# SCH_Logette_connect__2023-11-30.net
KiCad netlist of a schematic drawn in EasyEDA
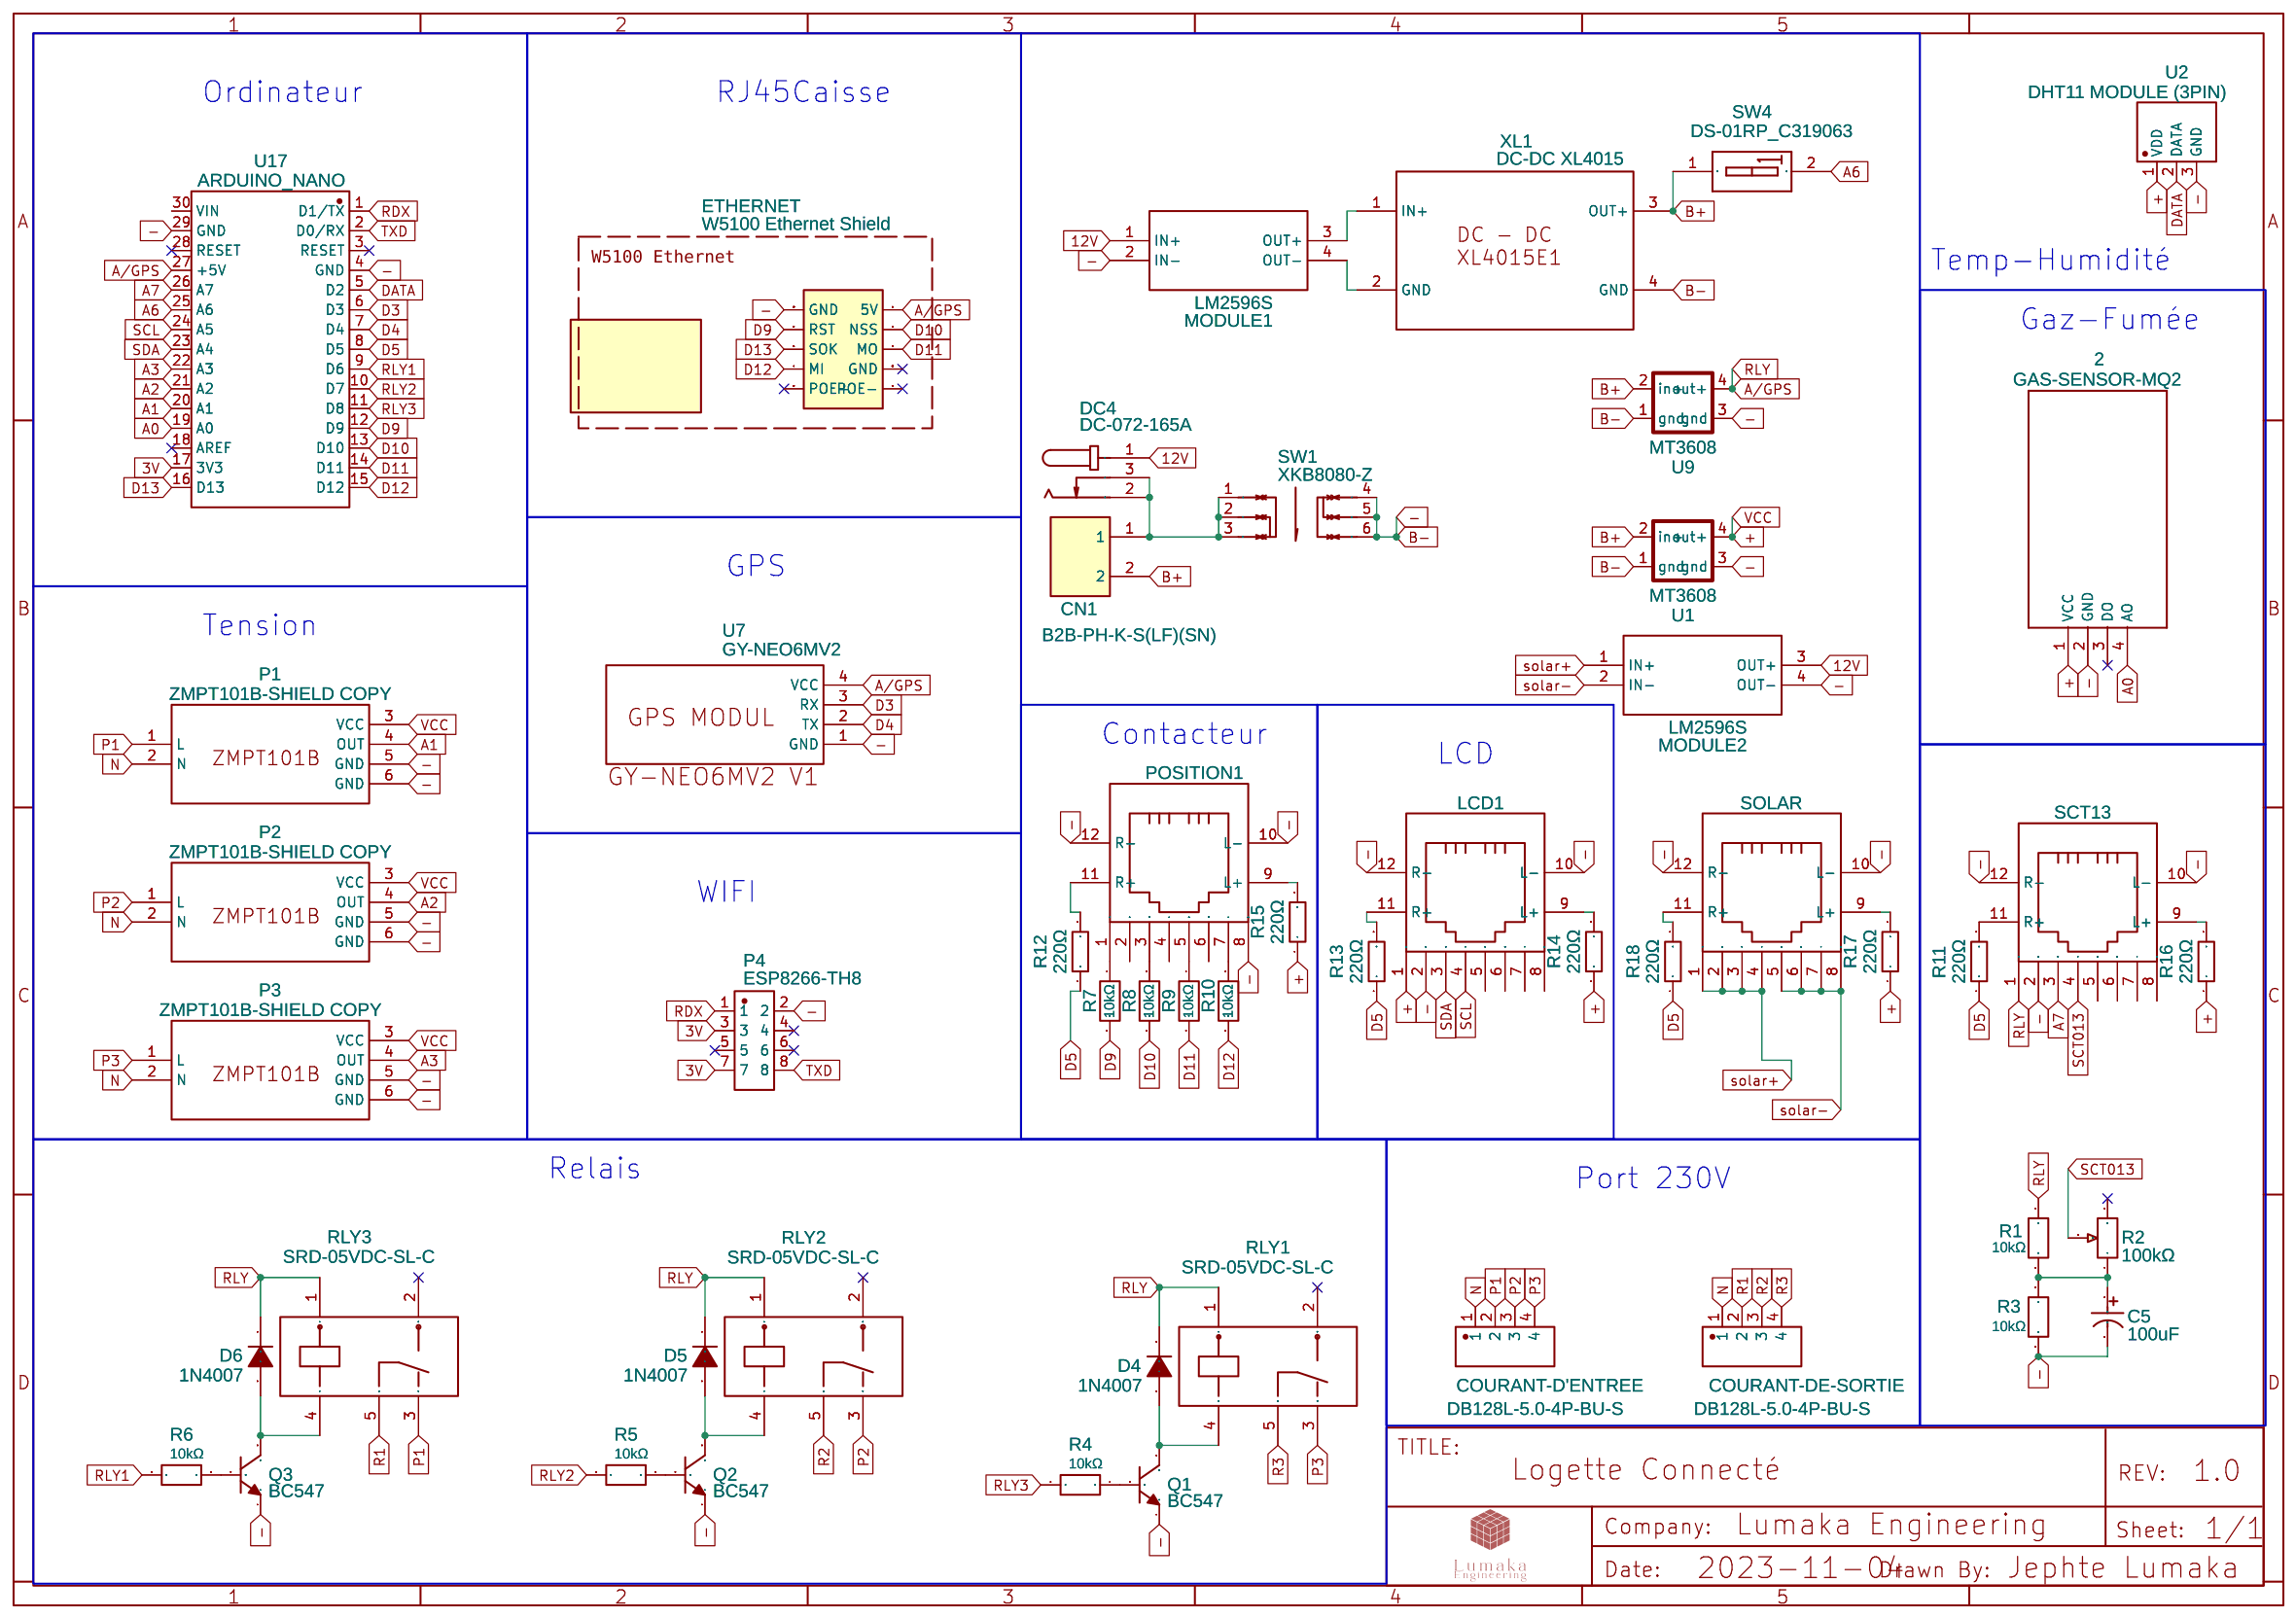
[diagram p0: schematic sheet]

(export (version "E")
  (design (tool "Eeschema 10.0.6"))
  (components
    (comp (ref "2") (value "GAS-SENSOR-MQ2") (libsource (lib "") (part "GAS-SENSOR-MQ2")))
    (comp (ref "C5")
      (value "100uF")
      (fields
        (field (name "Manufacturer Part") "UWX1C101MCL1GB")
        (field (name "Manufacturer") "Nichicon(尼吉康)")
      )
      (libsource (lib "") (part "UWX1C101MCL1GB"))
    )
    (comp (ref "CN1")
      (value "B2B-PH-K-S(LF)(SN)")
      (fields (field (name "Manufacturer") "JST"))
      (libsource (lib "") (part "B2B-PH-K-S(LF)(SN)"))
    )
    (comp (ref "COURANT-D'ENTREE")
      (value "DB128L-5.0-4P-BU-S")
      (fields (field (name "Manufacturer") "DIBO(地博电气)"))
      (libsource (lib "") (part "DB128L-5.0-4P-BU-S_1"))
    )
    (comp (ref "COURANT-DE-SORTIE")
      (value "DB128L-5.0-4P-BU-S")
      (fields (field (name "Manufacturer") "DIBO(地博电气)"))
      (libsource (lib "") (part "DB128L-5.0-4P-BU-S"))
    )
    (comp (ref "D4")
      (value "1N4007")
      (fields (field (name "Manufacturer Part") "1N4007E-E3/54") (field (name "Manufacturer") "VISHAY(威世)"))
      (libsource (lib "") (part "1N4007E-E3/54"))
    )
    (comp (ref "D5")
      (value "1N4007")
      (fields (field (name "Manufacturer Part") "1N4007E-E3/54") (field (name "Manufacturer") "VISHAY(威世)"))
      (libsource (lib "") (part "1N4007E-E3/54"))
    )
    (comp (ref "D6")
      (value "1N4007")
      (fields (field (name "Manufacturer Part") "1N4007E-E3/54") (field (name "Manufacturer") "VISHAY(威世)"))
      (libsource (lib "") (part "1N4007E-E3/54"))
    )
    (comp (ref "DC4")
      (value "DC-072-165A")
      (fields (field (name "Manufacturer") "HRO"))
      (libsource (lib "") (part "DC-072-165A"))
    )
    (comp (ref "ETHERNET")
      (value "W5100 Ethernet Shield")
      (libsource (lib "") (part "W5100 Ethernet Shield"))
    )
    (comp (ref "LCD1")
      (value "MJ5688-Y011-GRNL1")
      (fields (field (name "Manufacturer") "Heling(合陵)"))
      (libsource (lib "") (part "MJ5688-Y011-GRNL1_3"))
    )
    (comp (ref "MODULE1")
      (value "LM2596S")
      (fields (field (name "Manufacturer Part") "LM2596"))
      (libsource (lib "") (part "LM2596S"))
    )
    (comp (ref "MODULE2")
      (value "LM2596S")
      (fields (field (name "Manufacturer Part") "LM2596"))
      (libsource (lib "") (part "LM2596S"))
    )
    (comp (ref "P1")
      (value "ZMPT101B-SHIELD COPY")
      (fields (field (name "Manufacturer") "sterling"))
      (libsource (lib "") (part "ZMPT101B-SHIELD COPY"))
    )
    (comp (ref "P2")
      (value "ZMPT101B-SHIELD COPY")
      (fields (field (name "Manufacturer") "sterling"))
      (libsource (lib "") (part "ZMPT101B-SHIELD COPY"))
    )
    (comp (ref "P3")
      (value "ZMPT101B-SHIELD COPY")
      (fields (field (name "Manufacturer") "sterling"))
      (libsource (lib "") (part "ZMPT101B-SHIELD COPY"))
    )
    (comp (ref "P4") (value "ESP8266-TH8") (libsource (lib "") (part "ESP8266-TH8")))
    (comp (ref "POSITION1")
      (value "MJ5688-Y011-GRNL1")
      (fields (field (name "Manufacturer") "Heling(合陵)"))
      (libsource (lib "") (part "MJ5688-Y011-GRNL1_1"))
    )
    (comp (ref "Q1") (value "BC547") (libsource (lib "") (part "BC547COPY")))
    (comp (ref "Q2") (value "BC547") (libsource (lib "") (part "BC547COPY")))
    (comp (ref "Q3") (value "BC547") (libsource (lib "") (part "BC547COPY")))
    (comp (ref "R1")
      (value "10kΩ")
      (fields
        (field (name "Manufacturer Part") "MF1/4W-100KΩ±1%T52")
        (field (name "Manufacturer") "Huaxing Mechanical-Elec.")
      )
      (libsource (lib "") (part "MF1/4W-100KΩ±1%T52"))
    )
    (comp (ref "R2")
      (value "100kΩ")
      (fields (field (name "Manufacturer Part") "3296W-1-104") (field (name "Manufacturer") "BOCHEN(博晨)"))
      (libsource (lib "") (part "3296W-1-104"))
    )
    (comp (ref "R3")
      (value "10kΩ")
      (fields
        (field (name "Manufacturer Part") "MF1/4W-100KΩ±1%T52")
        (field (name "Manufacturer") "Huaxing Mechanical-Elec.")
      )
      (libsource (lib "") (part "MF1/4W-100KΩ±1%T52"))
    )
    (comp (ref "R4")
      (value "10kΩ")
      (fields
        (field (name "Manufacturer Part") "MF1/4W-100KΩ±1%T52")
        (field (name "Manufacturer") "Huaxing Mechanical-Elec.")
      )
      (libsource (lib "") (part "MF1/4W-100KΩ±1%T52_1"))
    )
    (comp (ref "R5")
      (value "10kΩ")
      (fields
        (field (name "Manufacturer Part") "MF1/4W-100KΩ±1%T52")
        (field (name "Manufacturer") "Huaxing Mechanical-Elec.")
      )
      (libsource (lib "") (part "MF1/4W-100KΩ±1%T52_1"))
    )
    (comp (ref "R6")
      (value "10kΩ")
      (fields
        (field (name "Manufacturer Part") "MF1/4W-100KΩ±1%T52")
        (field (name "Manufacturer") "Huaxing Mechanical-Elec.")
      )
      (libsource (lib "") (part "MF1/4W-100KΩ±1%T52_1"))
    )
    (comp (ref "R7")
      (value "10kΩ")
      (fields
        (field (name "Manufacturer Part") "MF1/4W-100KΩ±1%T52")
        (field (name "Manufacturer") "Huaxing Mechanical-Elec.")
      )
      (libsource (lib "") (part "MF1/4W-100KΩ±1%T52"))
    )
    (comp (ref "R8")
      (value "10kΩ")
      (fields
        (field (name "Manufacturer Part") "MF1/4W-100KΩ±1%T52")
        (field (name "Manufacturer") "Huaxing Mechanical-Elec.")
      )
      (libsource (lib "") (part "MF1/4W-100KΩ±1%T52"))
    )
    (comp (ref "R9")
      (value "10kΩ")
      (fields
        (field (name "Manufacturer Part") "MF1/4W-100KΩ±1%T52")
        (field (name "Manufacturer") "Huaxing Mechanical-Elec.")
      )
      (libsource (lib "") (part "MF1/4W-100KΩ±1%T52"))
    )
    (comp (ref "R10")
      (value "10kΩ")
      (fields
        (field (name "Manufacturer Part") "MF1/4W-100KΩ±1%T52")
        (field (name "Manufacturer") "Huaxing Mechanical-Elec.")
      )
      (libsource (lib "") (part "MF1/4W-100KΩ±1%T52"))
    )
    (comp (ref "R11")
      (value "220Ω")
      (fields
        (field (name "Manufacturer Part") "MFR0W4F2200A50")
        (field (name "Manufacturer") "UNI-ROYAL(厚声)")
      )
      (libsource (lib "") (part "MFR0W4F2200A50"))
    )
    (comp (ref "R12")
      (value "220Ω")
      (fields
        (field (name "Manufacturer Part") "MFR0W4F2200A50")
        (field (name "Manufacturer") "UNI-ROYAL(厚声)")
      )
      (libsource (lib "") (part "MFR0W4F2200A50"))
    )
    (comp (ref "R13")
      (value "220Ω")
      (fields
        (field (name "Manufacturer Part") "MFR0W4F2200A50")
        (field (name "Manufacturer") "UNI-ROYAL(厚声)")
      )
      (libsource (lib "") (part "MFR0W4F2200A50"))
    )
    (comp (ref "R14")
      (value "220Ω")
      (fields
        (field (name "Manufacturer Part") "MFR0W4F2200A50")
        (field (name "Manufacturer") "UNI-ROYAL(厚声)")
      )
      (libsource (lib "") (part "MFR0W4F2200A50"))
    )
    (comp (ref "R15")
      (value "220Ω")
      (fields
        (field (name "Manufacturer Part") "MFR0W4F2200A50")
        (field (name "Manufacturer") "UNI-ROYAL(厚声)")
      )
      (libsource (lib "") (part "MFR0W4F2200A50"))
    )
    (comp (ref "R16")
      (value "220Ω")
      (fields
        (field (name "Manufacturer Part") "MFR0W4F2200A50")
        (field (name "Manufacturer") "UNI-ROYAL(厚声)")
      )
      (libsource (lib "") (part "MFR0W4F2200A50"))
    )
    (comp (ref "R17")
      (value "220Ω")
      (fields
        (field (name "Manufacturer Part") "MFR0W4F2200A50")
        (field (name "Manufacturer") "UNI-ROYAL(厚声)")
      )
      (libsource (lib "") (part "MFR0W4F2200A50"))
    )
    (comp (ref "R18")
      (value "220Ω")
      (fields
        (field (name "Manufacturer Part") "MFR0W4F2200A50")
        (field (name "Manufacturer") "UNI-ROYAL(厚声)")
      )
      (libsource (lib "") (part "MFR0W4F2200A50"))
    )
    (comp (ref "RLY1")
      (value "SRD-05VDC-SL-C")
      (fields (field (name "Manufacturer") "松乐"))
      (libsource (lib "") (part "SRD-05VDC-SL-C"))
    )
    (comp (ref "RLY2")
      (value "SRD-05VDC-SL-C")
      (fields (field (name "Manufacturer") "松乐"))
      (libsource (lib "") (part "SRD-05VDC-SL-C"))
    )
    (comp (ref "RLY3")
      (value "SRD-05VDC-SL-C")
      (fields (field (name "Manufacturer") "松乐"))
      (libsource (lib "") (part "SRD-05VDC-SL-C"))
    )
    (comp (ref "SCT13")
      (value "MJ5688-Y011-GRNL1")
      (fields (field (name "Manufacturer") "Heling(合陵)"))
      (libsource (lib "") (part "MJ5688-Y011-GRNL1"))
    )
    (comp (ref "SOLAR")
      (value "MJ5688-Y011-GRNL1")
      (fields (field (name "Manufacturer") "Heling(合陵)"))
      (libsource (lib "") (part "MJ5688-Y011-GRNL1_2"))
    )
    (comp (ref "SW1")
      (value "XKB8080-Z")
      (fields (field (name "Manufacturer") "XKB Enterprise"))
      (libsource (lib "") (part "XKB8080-Z"))
    )
    (comp (ref "SW4")
      (value "DS-01RP_C319063")
      (fields (field (name "Manufacturer Part") "DS-01RP") (field (name "Manufacturer") "XKB Enterprise"))
      (libsource (lib "") (part "DS-01RP_C319063"))
    )
    (comp (ref "U1")
      (value "MT3608")
      (fields (field (name "Manufacturer Part") "dc/dc"))
      (libsource (lib "") (part "dc dc"))
    )
    (comp (ref "U2")
      (value "DHT11 MODULE (3PIN)")
      (fields
        (field (name "Manufacturer Part") "DHT11")
        (field (name "Manufacturer") "Aosong (Guangzhou) Elec")
      )
      (libsource (lib "") (part "DHT11 MODULE (3PIN)"))
    )
    (comp (ref "U7") (value "GY-NEO6MV2") (libsource (lib "") (part "GY-NEO6MV2")))
    (comp (ref "U9")
      (value "MT3608")
      (fields (field (name "Manufacturer Part") "dc/dc"))
      (libsource (lib "") (part "dc dc"))
    )
    (comp (ref "U17") (value "ARDUINO_NANO") (libsource (lib "") (part "ARDUINO_NANO")))
    (comp (ref "XL1") (value "DC-DC XL4015") (libsource (lib "") (part "DC-DC XL4015")))
  )
  (nets
    (net (code "1") (name "+") (class "Default")
      (node (ref "2") (pin "1") (pinfunction "VCC_1") (pintype "bidirectional"))
      (node (ref "LCD1") (pin "1") (pinfunction "1_1") (pintype "unspecified"))
      (node (ref "P1") (pin "3") (pinfunction "VCC_3") (pintype "unspecified"))
      (node (ref "P2") (pin "3") (pinfunction "VCC_3") (pintype "unspecified"))
      (node (ref "P3") (pin "3") (pinfunction "VCC_3") (pintype "unspecified"))
      (node (ref "R14") (pin "1") (pinfunction "1_1") (pintype "input"))
      (node (ref "R15") (pin "1") (pinfunction "1_1") (pintype "input"))
      (node (ref "R16") (pin "1") (pinfunction "1_1") (pintype "input"))
      (node (ref "R17") (pin "1") (pinfunction "1_1") (pintype "input"))
      (node (ref "U1") (pin "4") (pinfunction "out+_4") (pintype "unspecified"))
      (node (ref "U2") (pin "1") (pinfunction "VDD_1") (pintype "unspecified"))
    )
    (net (code "2") (name "-") (class "Default")
      (node (ref "2") (pin "2") (pinfunction "GND_2") (pintype "bidirectional"))
      (node (ref "C5") (pin "2") (pinfunction "2_2") (pintype "input"))
      (node (ref "ETHERNET") (pin "GND_1") (pinfunction "GND_GND_1") (pintype "unspecified"))
      (node (ref "LCD1") (pin "10") (pinfunction "L-_10") (pintype "unspecified"))
      (node (ref "LCD1") (pin "12") (pinfunction "R-_12") (pintype "unspecified"))
      (node (ref "LCD1") (pin "2") (pinfunction "2_2") (pintype "unspecified"))
      (node (ref "MODULE1") (pin "2") (pinfunction "IN-_2") (pintype "input"))
      (node (ref "MODULE2") (pin "4") (pinfunction "OUT-_4") (pintype "output"))
      (node (ref "P1") (pin "5") (pinfunction "GND_5") (pintype "unspecified"))
      (node (ref "P1") (pin "6") (pinfunction "GND_6") (pintype "unspecified"))
      (node (ref "P2") (pin "5") (pinfunction "GND_5") (pintype "unspecified"))
      (node (ref "P2") (pin "6") (pinfunction "GND_6") (pintype "unspecified"))
      (node (ref "P3") (pin "5") (pinfunction "GND_5") (pintype "unspecified"))
      (node (ref "P3") (pin "6") (pinfunction "GND_6") (pintype "unspecified"))
      (node (ref "P4") (pin "2") (pinfunction "2_2") (pintype "unspecified"))
      (node (ref "POSITION1") (pin "10") (pinfunction "L-_10") (pintype "unspecified"))
      (node (ref "POSITION1") (pin "12") (pinfunction "R-_12") (pintype "unspecified"))
      (node (ref "POSITION1") (pin "8") (pinfunction "8_8") (pintype "unspecified"))
      (node (ref "Q1") (pin "1") (pinfunction "E_1") (pintype "unspecified"))
      (node (ref "Q2") (pin "1") (pinfunction "E_1") (pintype "unspecified"))
      (node (ref "Q3") (pin "1") (pinfunction "E_1") (pintype "unspecified"))
      (node (ref "R3") (pin "2") (pinfunction "2_2") (pintype "unspecified"))
      (node (ref "SCT13") (pin "10") (pinfunction "L-_10") (pintype "unspecified"))
      (node (ref "SCT13") (pin "12") (pinfunction "R-_12") (pintype "unspecified"))
      (node (ref "SCT13") (pin "2") (pinfunction "2_2") (pintype "unspecified"))
      (node (ref "SOLAR") (pin "10") (pinfunction "L-_10") (pintype "unspecified"))
      (node (ref "SOLAR") (pin "12") (pinfunction "R-_12") (pintype "unspecified"))
      (node (ref "SW1") (pin "4") (pinfunction "4_4") (pintype "unspecified"))
      (node (ref "SW1") (pin "5") (pinfunction "5_5") (pintype "unspecified"))
      (node (ref "SW1") (pin "6") (pinfunction "6_6") (pintype "unspecified"))
      (node (ref "U1") (pin "1") (pinfunction "gnd_1") (pintype "unspecified"))
      (node (ref "U1") (pin "3") (pinfunction "gnd_3") (pintype "unspecified"))
      (node (ref "U17") (pin "29") (pinfunction "GND_29") (pintype "unspecified"))
      (node (ref "U17") (pin "4") (pinfunction "GND_4") (pintype "unspecified"))
      (node (ref "U2") (pin "3") (pinfunction "GND_3") (pintype "unspecified"))
      (node (ref "U7") (pin "1") (pinfunction "GND_1") (pintype "passive"))
      (node (ref "U9") (pin "1") (pinfunction "gnd_1") (pintype "unspecified"))
      (node (ref "U9") (pin "3") (pinfunction "gnd_3") (pintype "unspecified"))
      (node (ref "XL1") (pin "4") (pinfunction "GND_4") (pintype "unspecified"))
    )
    (net (code "3") (name "3V") (class "Default")
      (node (ref "P4") (pin "3") (pinfunction "3_3") (pintype "unspecified"))
      (node (ref "P4") (pin "7") (pinfunction "7_7") (pintype "unspecified"))
      (node (ref "U17") (pin "17") (pinfunction "3V3_17") (pintype "unspecified"))
    )
    (net (code "4") (name "12V") (class "Default")
      (node (ref "DC4") (pin "1") (pinfunction "1_1") (pintype "unspecified"))
      (node (ref "MODULE1") (pin "1") (pinfunction "IN+_1") (pintype "input"))
      (node (ref "MODULE2") (pin "3") (pinfunction "OUT+_3") (pintype "output"))
    )
    (net (code "5") (name "A0") (class "Default")
      (node (ref "2") (pin "4") (pinfunction "AO_4") (pintype "bidirectional"))
      (node (ref "U17") (pin "19") (pinfunction "A0_19") (pintype "unspecified"))
    )
    (net (code "6") (name "A1") (class "Default")
      (node (ref "P1") (pin "4") (pinfunction "OUT_4") (pintype "unspecified"))
      (node (ref "U17") (pin "20") (pinfunction "A1_20") (pintype "unspecified"))
    )
    (net (code "7") (name "A2") (class "Default")
      (node (ref "P2") (pin "4") (pinfunction "OUT_4") (pintype "unspecified"))
      (node (ref "U17") (pin "21") (pinfunction "A2_21") (pintype "unspecified"))
    )
    (net (code "8") (name "A3") (class "Default")
      (node (ref "P3") (pin "4") (pinfunction "OUT_4") (pintype "unspecified"))
      (node (ref "U17") (pin "22") (pinfunction "A3_22") (pintype "unspecified"))
    )
    (net (code "9") (name "A6") (class "Default")
      (node (ref "SW4") (pin "2") (pinfunction "A2_2") (pintype "input"))
      (node (ref "U17") (pin "25") (pinfunction "A6_25") (pintype "unspecified"))
    )
    (net (code "10") (name "A7") (class "Default")
      (node (ref "SCT13") (pin "3") (pinfunction "3_3") (pintype "unspecified"))
      (node (ref "U17") (pin "26") (pinfunction "A7_26") (pintype "unspecified"))
    )
    (net (code "11") (name "A{slash}GPS") (class "Default")
      (node (ref "D4") (pin "1") (pinfunction "K_1") (pintype "unspecified"))
      (node (ref "D5") (pin "1") (pinfunction "K_1") (pintype "unspecified"))
      (node (ref "D6") (pin "1") (pinfunction "K_1") (pintype "unspecified"))
      (node (ref "ETHERNET") (pin "5V") (pinfunction "5V_5V") (pintype "unspecified"))
      (node (ref "R1") (pin "1") (pinfunction "1_1") (pintype "unspecified"))
      (node (ref "RLY1") (pin "1") (pinfunction "1_1") (pintype "input"))
      (node (ref "RLY2") (pin "1") (pinfunction "1_1") (pintype "input"))
      (node (ref "RLY3") (pin "1") (pinfunction "1_1") (pintype "input"))
      (node (ref "SCT13") (pin "1") (pinfunction "1_1") (pintype "unspecified"))
      (node (ref "U17") (pin "27") (pinfunction "+5V_27") (pintype "unspecified"))
      (node (ref "U7") (pin "4") (pinfunction "VCC_4") (pintype "passive"))
      (node (ref "U9") (pin "4") (pinfunction "out+_4") (pintype "unspecified"))
    )
    (net (code "12") (name "B+") (class "Default")
      (node (ref "CN1") (pin "2") (pinfunction "2_2") (pintype "input"))
      (node (ref "SW4") (pin "1") (pinfunction "A1_1") (pintype "input"))
      (node (ref "U1") (pin "2") (pinfunction "in+_2") (pintype "unspecified"))
      (node (ref "U9") (pin "2") (pinfunction "in+_2") (pintype "unspecified"))
      (node (ref "XL1") (pin "3") (pinfunction "OUT+_3") (pintype "passive"))
    )
    (net (code "13") (name "D3") (class "Default")
      (node (ref "U17") (pin "6") (pinfunction "D3_6") (pintype "unspecified"))
      (node (ref "U7") (pin "3") (pinfunction "RX_3") (pintype "input"))
    )
    (net (code "14") (name "D4") (class "Default")
      (node (ref "U17") (pin "7") (pinfunction "D4_7") (pintype "unspecified"))
      (node (ref "U7") (pin "2") (pinfunction "TX_2") (pintype "output"))
    )
    (net (code "15") (name "D5") (class "Default")
      (node (ref "R11") (pin "1") (pinfunction "1_1") (pintype "input"))
      (node (ref "R12") (pin "1") (pinfunction "1_1") (pintype "input"))
      (node (ref "R13") (pin "1") (pinfunction "1_1") (pintype "input"))
      (node (ref "R18") (pin "1") (pinfunction "1_1") (pintype "input"))
      (node (ref "U17") (pin "8") (pinfunction "D5_8") (pintype "unspecified"))
    )
    (net (code "16") (name "D9") (class "Default")
      (node (ref "ETHERNET") (pin "RST") (pinfunction "RST_RST") (pintype "unspecified"))
      (node (ref "R7") (pin "2") (pinfunction "2_2") (pintype "unspecified"))
      (node (ref "U17") (pin "12") (pinfunction "D9_12") (pintype "unspecified"))
    )
    (net (code "17") (name "D10") (class "Default")
      (node (ref "ETHERNET") (pin "NSS") (pinfunction "NSS_NSS") (pintype "unspecified"))
      (node (ref "R8") (pin "2") (pinfunction "2_2") (pintype "unspecified"))
      (node (ref "U17") (pin "13") (pinfunction "D10_13") (pintype "unspecified"))
    )
    (net (code "18") (name "D11") (class "Default")
      (node (ref "ETHERNET") (pin "MO") (pinfunction "MO_MO") (pintype "unspecified"))
      (node (ref "R9") (pin "2") (pinfunction "2_2") (pintype "unspecified"))
      (node (ref "U17") (pin "14") (pinfunction "D11_14") (pintype "unspecified"))
    )
    (net (code "19") (name "D12") (class "Default")
      (node (ref "ETHERNET") (pin "MI") (pinfunction "MI_MI") (pintype "unspecified"))
      (node (ref "R10") (pin "2") (pinfunction "2_2") (pintype "unspecified"))
      (node (ref "U17") (pin "15") (pinfunction "D12_15") (pintype "unspecified"))
    )
    (net (code "20") (name "D13") (class "Default")
      (node (ref "ETHERNET") (pin "SOK") (pinfunction "SOK_SOK") (pintype "unspecified"))
      (node (ref "U17") (pin "16") (pinfunction "D13_16") (pintype "unspecified"))
    )
    (net (code "21") (name "DATA") (class "Default")
      (node (ref "U17") (pin "5") (pinfunction "D2_5") (pintype "unspecified"))
      (node (ref "U2") (pin "2") (pinfunction "DATA_2") (pintype "unspecified"))
    )
    (net (code "22") (name "N") (class "Default")
      (node (ref "COURANT-D'ENTREE") (pin "1") (pinfunction "1_1") (pintype "unspecified"))
      (node (ref "COURANT-DE-SORTIE") (pin "1") (pinfunction "1_1") (pintype "unspecified"))
      (node (ref "P1") (pin "2") (pinfunction "N_2") (pintype "unspecified"))
      (node (ref "P2") (pin "2") (pinfunction "N_2") (pintype "unspecified"))
      (node (ref "P3") (pin "2") (pinfunction "N_2") (pintype "unspecified"))
    )
    (net (code "23") (name "Net-(C5-Pad1)") (class "Default")
      (node (ref "C5") (pin "1") (pinfunction "1_1") (pintype "input"))
      (node (ref "R1") (pin "2") (pinfunction "2_2") (pintype "unspecified"))
      (node (ref "R2") (pin "1") (pinfunction "1_1") (pintype "input"))
      (node (ref "R3") (pin "1") (pinfunction "1_1") (pintype "unspecified"))
    )
    (net (code "24") (name "Net-(CN1-Pad1)") (class "Default")
      (node (ref "CN1") (pin "1") (pinfunction "1_1") (pintype "input"))
      (node (ref "DC4") (pin "2") (pinfunction "2_2") (pintype "unspecified"))
      (node (ref "DC4") (pin "3") (pinfunction "3_3") (pintype "unspecified"))
      (node (ref "SW1") (pin "1") (pinfunction "1_1") (pintype "unspecified"))
      (node (ref "SW1") (pin "2") (pinfunction "2_2") (pintype "unspecified"))
      (node (ref "SW1") (pin "3") (pinfunction "3_3") (pintype "unspecified"))
    )
    (net (code "25") (name "Net-(D4-A)") (class "Default")
      (node (ref "D4") (pin "2") (pinfunction "A_2") (pintype "unspecified"))
      (node (ref "Q1") (pin "3") (pinfunction "C_3") (pintype "unspecified"))
      (node (ref "RLY1") (pin "4") (pinfunction "4_4") (pintype "input"))
    )
    (net (code "26") (name "Net-(D5-A)") (class "Default")
      (node (ref "D5") (pin "2") (pinfunction "A_2") (pintype "unspecified"))
      (node (ref "Q2") (pin "3") (pinfunction "C_3") (pintype "unspecified"))
      (node (ref "RLY2") (pin "4") (pinfunction "4_4") (pintype "input"))
    )
    (net (code "27") (name "Net-(D6-A)") (class "Default")
      (node (ref "D6") (pin "2") (pinfunction "A_2") (pintype "unspecified"))
      (node (ref "Q3") (pin "3") (pinfunction "C_3") (pintype "unspecified"))
      (node (ref "RLY3") (pin "4") (pinfunction "4_4") (pintype "input"))
    )
    (net (code "28") (name "Net-(LCD1-L+)") (class "Default")
      (node (ref "LCD1") (pin "9") (pinfunction "L+_9") (pintype "unspecified"))
      (node (ref "R14") (pin "2") (pinfunction "2_2") (pintype "input"))
    )
    (net (code "29") (name "Net-(LCD1-R+)") (class "Default")
      (node (ref "LCD1") (pin "11") (pinfunction "R+_11") (pintype "unspecified"))
      (node (ref "R13") (pin "2") (pinfunction "2_2") (pintype "input"))
    )
    (net (code "30") (name "Net-(MODULE1-OUT+)") (class "Default")
      (node (ref "MODULE1") (pin "3") (pinfunction "OUT+_3") (pintype "output"))
      (node (ref "XL1") (pin "1") (pinfunction "IN+_1") (pintype "passive"))
    )
    (net (code "31") (name "Net-(MODULE1-OUT-)") (class "Default")
      (node (ref "MODULE1") (pin "4") (pinfunction "OUT-_4") (pintype "output"))
      (node (ref "XL1") (pin "2") (pinfunction "GND_2") (pintype "unspecified"))
    )
    (net (code "32") (name "Net-(POSITION1-L+)") (class "Default")
      (node (ref "POSITION1") (pin "9") (pinfunction "L+_9") (pintype "unspecified"))
      (node (ref "R15") (pin "2") (pinfunction "2_2") (pintype "input"))
    )
    (net (code "33") (name "Net-(POSITION1-Pad1)") (class "Default")
      (node (ref "POSITION1") (pin "1") (pinfunction "1_1") (pintype "unspecified"))
      (node (ref "R7") (pin "1") (pinfunction "1_1") (pintype "unspecified"))
    )
    (net (code "34") (name "Net-(POSITION1-Pad3)") (class "Default")
      (node (ref "POSITION1") (pin "3") (pinfunction "3_3") (pintype "unspecified"))
      (node (ref "R8") (pin "1") (pinfunction "1_1") (pintype "unspecified"))
    )
    (net (code "35") (name "Net-(POSITION1-Pad5)") (class "Default")
      (node (ref "POSITION1") (pin "5") (pinfunction "5_5") (pintype "unspecified"))
      (node (ref "R9") (pin "1") (pinfunction "1_1") (pintype "unspecified"))
    )
    (net (code "36") (name "Net-(POSITION1-Pad7)") (class "Default")
      (node (ref "POSITION1") (pin "7") (pinfunction "7_7") (pintype "unspecified"))
      (node (ref "R10") (pin "1") (pinfunction "1_1") (pintype "unspecified"))
    )
    (net (code "37") (name "Net-(POSITION1-R+)") (class "Default")
      (node (ref "POSITION1") (pin "11") (pinfunction "R+_11") (pintype "unspecified"))
      (node (ref "R12") (pin "2") (pinfunction "2_2") (pintype "input"))
    )
    (net (code "38") (name "Net-(Q1-B)") (class "Default")
      (node (ref "Q1") (pin "2") (pinfunction "B_2") (pintype "unspecified"))
      (node (ref "R4") (pin "1") (pinfunction "1_1") (pintype "unspecified"))
    )
    (net (code "39") (name "Net-(Q2-B)") (class "Default")
      (node (ref "Q2") (pin "2") (pinfunction "B_2") (pintype "unspecified"))
      (node (ref "R5") (pin "1") (pinfunction "1_1") (pintype "unspecified"))
    )
    (net (code "40") (name "Net-(Q3-B)") (class "Default")
      (node (ref "Q3") (pin "2") (pinfunction "B_2") (pintype "unspecified"))
      (node (ref "R6") (pin "1") (pinfunction "1_1") (pintype "unspecified"))
    )
    (net (code "41") (name "Net-(SCT13-L+)") (class "Default")
      (node (ref "R16") (pin "2") (pinfunction "2_2") (pintype "input"))
      (node (ref "SCT13") (pin "9") (pinfunction "L+_9") (pintype "unspecified"))
    )
    (net (code "42") (name "Net-(SCT13-R+)") (class "Default")
      (node (ref "R11") (pin "2") (pinfunction "2_2") (pintype "input"))
      (node (ref "SCT13") (pin "11") (pinfunction "R+_11") (pintype "unspecified"))
    )
    (net (code "43") (name "Net-(SOLAR-L+)") (class "Default")
      (node (ref "R17") (pin "2") (pinfunction "2_2") (pintype "input"))
      (node (ref "SOLAR") (pin "9") (pinfunction "L+_9") (pintype "unspecified"))
    )
    (net (code "44") (name "Net-(SOLAR-R+)") (class "Default")
      (node (ref "R18") (pin "2") (pinfunction "2_2") (pintype "input"))
      (node (ref "SOLAR") (pin "11") (pinfunction "R+_11") (pintype "unspecified"))
    )
    (net (code "45") (name "P1") (class "Default")
      (node (ref "COURANT-D'ENTREE") (pin "2") (pinfunction "2_2") (pintype "unspecified"))
      (node (ref "P1") (pin "1") (pinfunction "L_1") (pintype "unspecified"))
      (node (ref "RLY3") (pin "3") (pinfunction "3_3") (pintype "input"))
    )
    (net (code "46") (name "P2") (class "Default")
      (node (ref "COURANT-D'ENTREE") (pin "3") (pinfunction "3_3") (pintype "unspecified"))
      (node (ref "P2") (pin "1") (pinfunction "L_1") (pintype "unspecified"))
      (node (ref "RLY2") (pin "3") (pinfunction "3_3") (pintype "input"))
    )
    (net (code "47") (name "P3") (class "Default")
      (node (ref "COURANT-D'ENTREE") (pin "4") (pinfunction "4_4") (pintype "unspecified"))
      (node (ref "P3") (pin "1") (pinfunction "L_1") (pintype "unspecified"))
      (node (ref "RLY1") (pin "3") (pinfunction "3_3") (pintype "input"))
    )
    (net (code "48") (name "R1") (class "Default")
      (node (ref "COURANT-DE-SORTIE") (pin "2") (pinfunction "2_2") (pintype "unspecified"))
      (node (ref "RLY3") (pin "5") (pinfunction "5_5") (pintype "input"))
    )
    (net (code "49") (name "R2") (class "Default")
      (node (ref "COURANT-DE-SORTIE") (pin "3") (pinfunction "3_3") (pintype "unspecified"))
      (node (ref "RLY2") (pin "5") (pinfunction "5_5") (pintype "input"))
    )
    (net (code "50") (name "R3") (class "Default")
      (node (ref "COURANT-DE-SORTIE") (pin "4") (pinfunction "4_4") (pintype "unspecified"))
      (node (ref "RLY1") (pin "5") (pinfunction "5_5") (pintype "input"))
    )
    (net (code "51") (name "RDX") (class "Default")
      (node (ref "P4") (pin "1") (pinfunction "1_1") (pintype "unspecified"))
      (node (ref "U17") (pin "1") (pinfunction "D1/TX_1") (pintype "unspecified"))
    )
    (net (code "52") (name "RLY1") (class "Default")
      (node (ref "R6") (pin "2") (pinfunction "2_2") (pintype "unspecified"))
      (node (ref "U17") (pin "9") (pinfunction "D6_9") (pintype "unspecified"))
    )
    (net (code "53") (name "RLY2") (class "Default")
      (node (ref "R5") (pin "2") (pinfunction "2_2") (pintype "unspecified"))
      (node (ref "U17") (pin "10") (pinfunction "D7_10") (pintype "unspecified"))
    )
    (net (code "54") (name "RLY3") (class "Default")
      (node (ref "R4") (pin "2") (pinfunction "2_2") (pintype "unspecified"))
      (node (ref "U17") (pin "11") (pinfunction "D8_11") (pintype "unspecified"))
    )
    (net (code "55") (name "SCL") (class "Default")
      (node (ref "LCD1") (pin "4") (pinfunction "4_4") (pintype "unspecified"))
      (node (ref "U17") (pin "24") (pinfunction "A5_24") (pintype "unspecified"))
    )
    (net (code "56") (name "SCT013") (class "Default")
      (node (ref "R2") (pin "2") (pinfunction "2_2") (pintype "input"))
      (node (ref "SCT13") (pin "4") (pinfunction "4_4") (pintype "unspecified"))
    )
    (net (code "57") (name "SDA") (class "Default")
      (node (ref "LCD1") (pin "3") (pinfunction "3_3") (pintype "unspecified"))
      (node (ref "U17") (pin "23") (pinfunction "A4_23") (pintype "unspecified"))
    )
    (net (code "58") (name "TXD") (class "Default")
      (node (ref "P4") (pin "8") (pinfunction "8_8") (pintype "unspecified"))
      (node (ref "U17") (pin "2") (pinfunction "D0/RX_2") (pintype "unspecified"))
    )
    (net (code "59") (name "solar+") (class "Default")
      (node (ref "MODULE2") (pin "1") (pinfunction "IN+_1") (pintype "input"))
      (node (ref "SOLAR") (pin "1") (pinfunction "1_1") (pintype "unspecified"))
      (node (ref "SOLAR") (pin "2") (pinfunction "2_2") (pintype "unspecified"))
      (node (ref "SOLAR") (pin "3") (pinfunction "3_3") (pintype "unspecified"))
      (node (ref "SOLAR") (pin "4") (pinfunction "4_4") (pintype "unspecified"))
    )
    (net (code "60") (name "solar-") (class "Default")
      (node (ref "MODULE2") (pin "2") (pinfunction "IN-_2") (pintype "input"))
      (node (ref "SOLAR") (pin "5") (pinfunction "5_5") (pintype "unspecified"))
      (node (ref "SOLAR") (pin "6") (pinfunction "6_6") (pintype "unspecified"))
      (node (ref "SOLAR") (pin "7") (pinfunction "7_7") (pintype "unspecified"))
      (node (ref "SOLAR") (pin "8") (pinfunction "8_8") (pintype "unspecified"))
    )
    (net (code "61") (name "unconnected-(2-DO-Pad3)") (class "Default")
      (node (ref "2") (pin "3") (pinfunction "DO_3") (pintype "bidirectional+no_connect"))
    )
    (net (code "62") (name "unconnected-(ETHERNET-GND-PadGND_2)") (class "Default")
      (node (ref "ETHERNET") (pin "GND_2") (pinfunction "GND_GND_2") (pintype "unspecified+no_connect"))
    )
    (net (code "63") (name "unconnected-(ETHERNET-PadPOE+)") (class "Default")
      (node (ref "ETHERNET") (pin "POE+") (pinfunction "POE+_POE+") (pintype "unspecified+no_connect"))
    )
    (net (code "64") (name "unconnected-(ETHERNET-PadPOE-)") (class "Default")
      (node (ref "ETHERNET") (pin "POE-") (pinfunction "POE-_POE-") (pintype "unspecified+no_connect"))
    )
    (net (code "65") (name "unconnected-(LCD1-Pad5)") (class "Default")
      (node (ref "LCD1") (pin "5") (pinfunction "5_5") (pintype "unspecified"))
    )
    (net (code "66") (name "unconnected-(LCD1-Pad6)") (class "Default")
      (node (ref "LCD1") (pin "6") (pinfunction "6_6") (pintype "unspecified"))
    )
    (net (code "67") (name "unconnected-(LCD1-Pad7)") (class "Default")
      (node (ref "LCD1") (pin "7") (pinfunction "7_7") (pintype "unspecified"))
    )
    (net (code "68") (name "unconnected-(LCD1-Pad8)") (class "Default")
      (node (ref "LCD1") (pin "8") (pinfunction "8_8") (pintype "unspecified"))
    )
    (net (code "69") (name "unconnected-(P4-Pad4)") (class "Default")
      (node (ref "P4") (pin "4") (pinfunction "4_4") (pintype "unspecified+no_connect"))
    )
    (net (code "70") (name "unconnected-(P4-Pad5)") (class "Default")
      (node (ref "P4") (pin "5") (pinfunction "5_5") (pintype "unspecified+no_connect"))
    )
    (net (code "71") (name "unconnected-(P4-Pad6)") (class "Default")
      (node (ref "P4") (pin "6") (pinfunction "6_6") (pintype "unspecified+no_connect"))
    )
    (net (code "72") (name "unconnected-(POSITION1-Pad2)") (class "Default")
      (node (ref "POSITION1") (pin "2") (pinfunction "2_2") (pintype "unspecified"))
    )
    (net (code "73") (name "unconnected-(POSITION1-Pad4)") (class "Default")
      (node (ref "POSITION1") (pin "4") (pinfunction "4_4") (pintype "unspecified"))
    )
    (net (code "74") (name "unconnected-(POSITION1-Pad6)") (class "Default")
      (node (ref "POSITION1") (pin "6") (pinfunction "6_6") (pintype "unspecified"))
    )
    (net (code "75") (name "unconnected-(R2-Pad3)") (class "Default")
      (node (ref "R2") (pin "3") (pinfunction "3_3") (pintype "input+no_connect"))
    )
    (net (code "76") (name "unconnected-(RLY1-Pad2)") (class "Default")
      (node (ref "RLY1") (pin "2") (pinfunction "2_2") (pintype "input+no_connect"))
    )
    (net (code "77") (name "unconnected-(RLY2-Pad2)") (class "Default")
      (node (ref "RLY2") (pin "2") (pinfunction "2_2") (pintype "input+no_connect"))
    )
    (net (code "78") (name "unconnected-(RLY3-Pad2)") (class "Default")
      (node (ref "RLY3") (pin "2") (pinfunction "2_2") (pintype "input+no_connect"))
    )
    (net (code "79") (name "unconnected-(SCT13-Pad5)") (class "Default")
      (node (ref "SCT13") (pin "5") (pinfunction "5_5") (pintype "unspecified"))
    )
    (net (code "80") (name "unconnected-(SCT13-Pad6)") (class "Default")
      (node (ref "SCT13") (pin "6") (pinfunction "6_6") (pintype "unspecified"))
    )
    (net (code "81") (name "unconnected-(SCT13-Pad7)") (class "Default")
      (node (ref "SCT13") (pin "7") (pinfunction "7_7") (pintype "unspecified"))
    )
    (net (code "82") (name "unconnected-(SCT13-Pad8)") (class "Default")
      (node (ref "SCT13") (pin "8") (pinfunction "8_8") (pintype "unspecified"))
    )
    (net (code "83") (name "unconnected-(U17-AREF-Pad18)") (class "Default")
      (node (ref "U17") (pin "18") (pinfunction "AREF_18") (pintype "unspecified+no_connect"))
    )
    (net (code "84") (name "unconnected-(U17-RESET-Pad3)") (class "Default")
      (node (ref "U17") (pin "3") (pinfunction "RESET_3") (pintype "unspecified+no_connect"))
    )
    (net (code "85") (name "unconnected-(U17-RESET-Pad28)") (class "Default")
      (node (ref "U17") (pin "28") (pinfunction "RESET_28") (pintype "unspecified+no_connect"))
    )
    (net (code "86") (name "unconnected-(U17-VIN-Pad30)") (class "Default")
      (node (ref "U17") (pin "30") (pinfunction "VIN_30") (pintype "unspecified"))
    )
  )
)
